# GPIO_LED_SW.net
KiCad netlist of a schematic drawn in Altium Designer
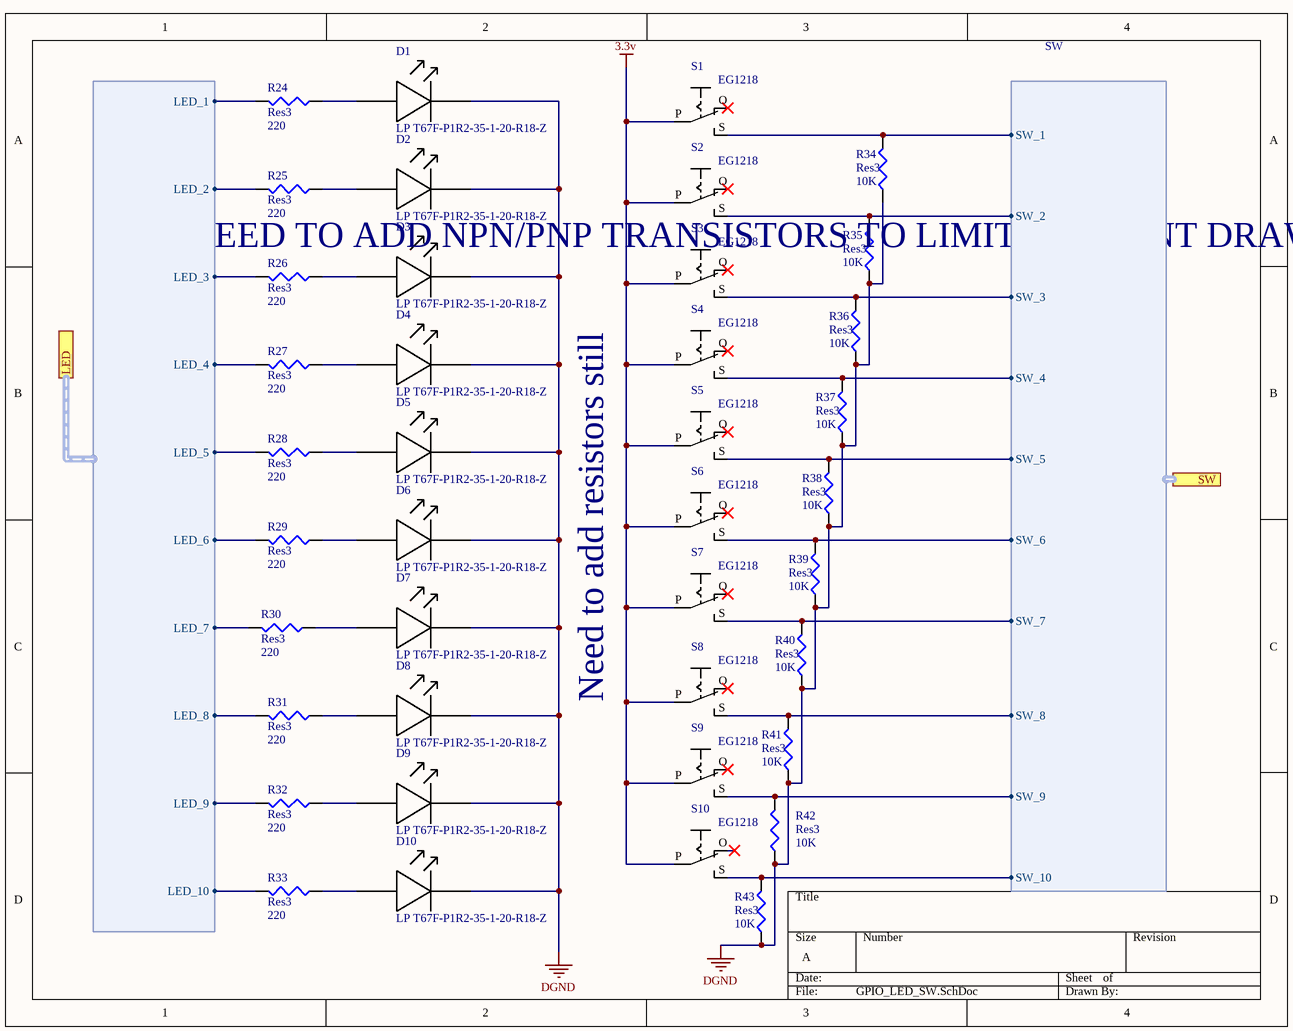
[diagram p0: GPIO_LED_SW.SchDoc]

(export (version "E")
  (design (tool "Eeschema 10.0.6"))
  (components
    (comp (ref "D1")
      (value "LP T67F-P1R2-35-1-20-R18-Z")
      (footprint "LP T67F-P1R2-35-1-20-R18-Z")
      (description "SMD LED")
      (libsource (lib "Components") (part "LP T67F-P1R2-35-1-20-R18-Z"))
    )
    (comp (ref "D2")
      (value "LP T67F-P1R2-35-1-20-R18-Z")
      (footprint "LP T67F-P1R2-35-1-20-R18-Z")
      (description "SMD LED")
      (libsource (lib "Components") (part "LP T67F-P1R2-35-1-20-R18-Z"))
    )
    (comp (ref "D3")
      (value "LP T67F-P1R2-35-1-20-R18-Z")
      (footprint "LP T67F-P1R2-35-1-20-R18-Z")
      (description "SMD LED")
      (libsource (lib "Components") (part "LP T67F-P1R2-35-1-20-R18-Z"))
    )
    (comp (ref "D4")
      (value "LP T67F-P1R2-35-1-20-R18-Z")
      (footprint "LP T67F-P1R2-35-1-20-R18-Z")
      (description "SMD LED")
      (libsource (lib "Components") (part "LP T67F-P1R2-35-1-20-R18-Z"))
    )
    (comp (ref "D5")
      (value "LP T67F-P1R2-35-1-20-R18-Z")
      (footprint "LP T67F-P1R2-35-1-20-R18-Z")
      (description "SMD LED")
      (libsource (lib "Components") (part "LP T67F-P1R2-35-1-20-R18-Z"))
    )
    (comp (ref "D6")
      (value "LP T67F-P1R2-35-1-20-R18-Z")
      (footprint "LP T67F-P1R2-35-1-20-R18-Z")
      (description "SMD LED")
      (libsource (lib "Components") (part "LP T67F-P1R2-35-1-20-R18-Z"))
    )
    (comp (ref "D7")
      (value "LP T67F-P1R2-35-1-20-R18-Z")
      (footprint "LP T67F-P1R2-35-1-20-R18-Z")
      (description "SMD LED")
      (libsource (lib "Components") (part "LP T67F-P1R2-35-1-20-R18-Z"))
    )
    (comp (ref "D8")
      (value "LP T67F-P1R2-35-1-20-R18-Z")
      (footprint "LP T67F-P1R2-35-1-20-R18-Z")
      (description "SMD LED")
      (libsource (lib "Components") (part "LP T67F-P1R2-35-1-20-R18-Z"))
    )
    (comp (ref "D9")
      (value "LP T67F-P1R2-35-1-20-R18-Z")
      (footprint "LP T67F-P1R2-35-1-20-R18-Z")
      (description "SMD LED")
      (libsource (lib "Components") (part "LP T67F-P1R2-35-1-20-R18-Z"))
    )
    (comp (ref "D10")
      (value "LP T67F-P1R2-35-1-20-R18-Z")
      (footprint "LP T67F-P1R2-35-1-20-R18-Z")
      (description "SMD LED")
      (libsource (lib "Components") (part "LP T67F-P1R2-35-1-20-R18-Z"))
    )
    (comp (ref "R24")
      (value "Res3")
      (footprint "J1-0603")
      (description "Resistor")
      (fields (field (name "ALTIUM_VALUE") "220") (field (name "PUBLISHER") "Altium Limited"))
      (libsource (lib "Miscellaneous Devices") (part "Res3"))
    )
    (comp (ref "R25")
      (value "Res3")
      (footprint "J1-0603")
      (description "Resistor")
      (fields (field (name "ALTIUM_VALUE") "220") (field (name "PUBLISHER") "Altium Limited"))
      (libsource (lib "Miscellaneous Devices") (part "Res3"))
    )
    (comp (ref "R26")
      (value "Res3")
      (footprint "J1-0603")
      (description "Resistor")
      (fields (field (name "ALTIUM_VALUE") "220") (field (name "PUBLISHER") "Altium Limited"))
      (libsource (lib "Miscellaneous Devices") (part "Res3"))
    )
    (comp (ref "R27")
      (value "Res3")
      (footprint "J1-0603")
      (description "Resistor")
      (fields (field (name "ALTIUM_VALUE") "220") (field (name "PUBLISHER") "Altium Limited"))
      (libsource (lib "Miscellaneous Devices") (part "Res3"))
    )
    (comp (ref "R28")
      (value "Res3")
      (footprint "J1-0603")
      (description "Resistor")
      (fields (field (name "ALTIUM_VALUE") "220") (field (name "PUBLISHER") "Altium Limited"))
      (libsource (lib "Miscellaneous Devices") (part "Res3"))
    )
    (comp (ref "R29")
      (value "Res3")
      (footprint "J1-0603")
      (description "Resistor")
      (fields (field (name "ALTIUM_VALUE") "220") (field (name "PUBLISHER") "Altium Limited"))
      (libsource (lib "Miscellaneous Devices") (part "Res3"))
    )
    (comp (ref "R30")
      (value "Res3")
      (footprint "J1-0603")
      (description "Resistor")
      (fields (field (name "ALTIUM_VALUE") "220") (field (name "PUBLISHER") "Altium Limited"))
      (libsource (lib "Miscellaneous Devices") (part "Res3"))
    )
    (comp (ref "R31")
      (value "Res3")
      (footprint "J1-0603")
      (description "Resistor")
      (fields (field (name "ALTIUM_VALUE") "220") (field (name "PUBLISHER") "Altium Limited"))
      (libsource (lib "Miscellaneous Devices") (part "Res3"))
    )
    (comp (ref "R32")
      (value "Res3")
      (footprint "J1-0603")
      (description "Resistor")
      (fields (field (name "ALTIUM_VALUE") "220") (field (name "PUBLISHER") "Altium Limited"))
      (libsource (lib "Miscellaneous Devices") (part "Res3"))
    )
    (comp (ref "R33")
      (value "Res3")
      (footprint "J1-0603")
      (description "Resistor")
      (fields (field (name "ALTIUM_VALUE") "220") (field (name "PUBLISHER") "Altium Limited"))
      (libsource (lib "Miscellaneous Devices") (part "Res3"))
    )
    (comp (ref "R34")
      (value "Res3")
      (footprint "J1-0603")
      (description "Resistor")
      (fields (field (name "ALTIUM_VALUE") "10K") (field (name "PUBLISHER") "Altium Limited"))
      (libsource (lib "Miscellaneous Devices") (part "Res3"))
    )
    (comp (ref "R35")
      (value "Res3")
      (footprint "J1-0603")
      (description "Resistor")
      (fields (field (name "ALTIUM_VALUE") "10K") (field (name "PUBLISHER") "Altium Limited"))
      (libsource (lib "Miscellaneous Devices") (part "Res3"))
    )
    (comp (ref "R36")
      (value "Res3")
      (footprint "J1-0603")
      (description "Resistor")
      (fields (field (name "ALTIUM_VALUE") "10K") (field (name "PUBLISHER") "Altium Limited"))
      (libsource (lib "Miscellaneous Devices") (part "Res3"))
    )
    (comp (ref "R37")
      (value "Res3")
      (footprint "J1-0603")
      (description "Resistor")
      (fields (field (name "ALTIUM_VALUE") "10K") (field (name "PUBLISHER") "Altium Limited"))
      (libsource (lib "Miscellaneous Devices") (part "Res3"))
    )
    (comp (ref "R38")
      (value "Res3")
      (footprint "J1-0603")
      (description "Resistor")
      (fields (field (name "ALTIUM_VALUE") "10K") (field (name "PUBLISHER") "Altium Limited"))
      (libsource (lib "Miscellaneous Devices") (part "Res3"))
    )
    (comp (ref "R39")
      (value "Res3")
      (footprint "J1-0603")
      (description "Resistor")
      (fields (field (name "ALTIUM_VALUE") "10K") (field (name "PUBLISHER") "Altium Limited"))
      (libsource (lib "Miscellaneous Devices") (part "Res3"))
    )
    (comp (ref "R40")
      (value "Res3")
      (footprint "J1-0603")
      (description "Resistor")
      (fields (field (name "ALTIUM_VALUE") "10K") (field (name "PUBLISHER") "Altium Limited"))
      (libsource (lib "Miscellaneous Devices") (part "Res3"))
    )
    (comp (ref "R41")
      (value "Res3")
      (footprint "J1-0603")
      (description "Resistor")
      (fields (field (name "ALTIUM_VALUE") "10K") (field (name "PUBLISHER") "Altium Limited"))
      (libsource (lib "Miscellaneous Devices") (part "Res3"))
    )
    (comp (ref "R42")
      (value "Res3")
      (footprint "J1-0603")
      (description "Resistor")
      (fields (field (name "ALTIUM_VALUE") "10K") (field (name "PUBLISHER") "Altium Limited"))
      (libsource (lib "Miscellaneous Devices") (part "Res3"))
    )
    (comp (ref "R43")
      (value "Res3")
      (footprint "J1-0603")
      (description "Resistor")
      (fields (field (name "ALTIUM_VALUE") "10K") (field (name "PUBLISHER") "Altium Limited"))
      (libsource (lib "Miscellaneous Devices") (part "Res3"))
    )
    (comp (ref "S1")
      (value "EG1218")
      (footprint "*EG1218_EG1218(Primary)")
      (description "Slide Switch SPDT Through Hole")
      (fields (field (name "MF") "E-Switch") (field (name "DIGI-KEY_PART_NUMBER") "EG1903-ND"))
      (libsource (lib "Components") (part "EG1218"))
    )
    (comp (ref "S2")
      (value "EG1218")
      (footprint "*EG1218_EG1218(Primary)")
      (description "Slide Switch SPDT Through Hole")
      (fields (field (name "MF") "E-Switch") (field (name "DIGI-KEY_PART_NUMBER") "EG1903-ND"))
      (libsource (lib "Components") (part "EG1218"))
    )
    (comp (ref "S3")
      (value "EG1218")
      (footprint "*EG1218_EG1218(Primary)")
      (description "Slide Switch SPDT Through Hole")
      (fields (field (name "MF") "E-Switch") (field (name "DIGI-KEY_PART_NUMBER") "EG1903-ND"))
      (libsource (lib "Components") (part "EG1218"))
    )
    (comp (ref "S4")
      (value "EG1218")
      (footprint "*EG1218_EG1218(Primary)")
      (description "Slide Switch SPDT Through Hole")
      (fields (field (name "MF") "E-Switch") (field (name "DIGI-KEY_PART_NUMBER") "EG1903-ND"))
      (libsource (lib "Components") (part "EG1218"))
    )
    (comp (ref "S5")
      (value "EG1218")
      (footprint "*EG1218_EG1218(Primary)")
      (description "Slide Switch SPDT Through Hole")
      (fields (field (name "MF") "E-Switch") (field (name "DIGI-KEY_PART_NUMBER") "EG1903-ND"))
      (libsource (lib "Components") (part "EG1218"))
    )
    (comp (ref "S6")
      (value "EG1218")
      (footprint "*EG1218_EG1218(Primary)")
      (description "Slide Switch SPDT Through Hole")
      (fields (field (name "MF") "E-Switch") (field (name "DIGI-KEY_PART_NUMBER") "EG1903-ND"))
      (libsource (lib "Components") (part "EG1218"))
    )
    (comp (ref "S7")
      (value "EG1218")
      (footprint "*EG1218_EG1218(Primary)")
      (description "Slide Switch SPDT Through Hole")
      (fields (field (name "MF") "E-Switch") (field (name "DIGI-KEY_PART_NUMBER") "EG1903-ND"))
      (libsource (lib "Components") (part "EG1218"))
    )
    (comp (ref "S8")
      (value "EG1218")
      (footprint "*EG1218_EG1218(Primary)")
      (description "Slide Switch SPDT Through Hole")
      (fields (field (name "MF") "E-Switch") (field (name "DIGI-KEY_PART_NUMBER") "EG1903-ND"))
      (libsource (lib "Components") (part "EG1218"))
    )
    (comp (ref "S9")
      (value "EG1218")
      (footprint "*EG1218_EG1218(Primary)")
      (description "Slide Switch SPDT Through Hole")
      (fields (field (name "MF") "E-Switch") (field (name "DIGI-KEY_PART_NUMBER") "EG1903-ND"))
      (libsource (lib "Components") (part "EG1218"))
    )
    (comp (ref "S10")
      (value "EG1218")
      (footprint "*EG1218_EG1218(Primary)")
      (description "Slide Switch SPDT Through Hole")
      (fields (field (name "MF") "E-Switch") (field (name "DIGI-KEY_PART_NUMBER") "EG1903-ND"))
      (libsource (lib "Components") (part "EG1218"))
    )
  )
  (nets
    (net (code "3") (name "/LED_1") (class "Default")
      (node (ref "R24") (pin "2") (pinfunction "2_2") (pintype "passive"))
    )
    (net (code "4") (name "/LED_2") (class "Default")
      (node (ref "R25") (pin "2") (pinfunction "2_2") (pintype "passive"))
    )
    (net (code "5") (name "/LED_3") (class "Default")
      (node (ref "R26") (pin "2") (pinfunction "2_2") (pintype "passive"))
    )
    (net (code "6") (name "/LED_4") (class "Default")
      (node (ref "R27") (pin "2") (pinfunction "2_2") (pintype "passive"))
    )
    (net (code "7") (name "/LED_5") (class "Default")
      (node (ref "R28") (pin "2") (pinfunction "2_2") (pintype "passive"))
    )
    (net (code "8") (name "/LED_6") (class "Default")
      (node (ref "R29") (pin "2") (pinfunction "2_2") (pintype "passive"))
    )
    (net (code "9") (name "/LED_7") (class "Default")
      (node (ref "R30") (pin "2") (pinfunction "2_2") (pintype "passive"))
    )
    (net (code "10") (name "/LED_8") (class "Default")
      (node (ref "R31") (pin "2") (pinfunction "2_2") (pintype "passive"))
    )
    (net (code "11") (name "/LED_9") (class "Default")
      (node (ref "R32") (pin "2") (pinfunction "2_2") (pintype "passive"))
    )
    (net (code "12") (name "/LED_10") (class "Default")
      (node (ref "R33") (pin "2") (pinfunction "2_2") (pintype "passive"))
    )
    (net (code "13") (name "/SW_1") (class "Default")
      (node (ref "R34") (pin "2") (pinfunction "2_2") (pintype "passive"))
      (node (ref "S1") (pin "S") (pinfunction "S_S") (pintype "passive"))
    )
    (net (code "14") (name "/SW_2") (class "Default")
      (node (ref "R35") (pin "2") (pinfunction "2_2") (pintype "passive"))
      (node (ref "S2") (pin "S") (pinfunction "S_S") (pintype "passive"))
    )
    (net (code "15") (name "/SW_3") (class "Default")
      (node (ref "R36") (pin "2") (pinfunction "2_2") (pintype "passive"))
      (node (ref "S3") (pin "S") (pinfunction "S_S") (pintype "passive"))
    )
    (net (code "16") (name "/SW_4") (class "Default")
      (node (ref "R37") (pin "2") (pinfunction "2_2") (pintype "passive"))
      (node (ref "S4") (pin "S") (pinfunction "S_S") (pintype "passive"))
    )
    (net (code "17") (name "/SW_5") (class "Default")
      (node (ref "R38") (pin "2") (pinfunction "2_2") (pintype "passive"))
      (node (ref "S5") (pin "S") (pinfunction "S_S") (pintype "passive"))
    )
    (net (code "18") (name "/SW_6") (class "Default")
      (node (ref "R39") (pin "2") (pinfunction "2_2") (pintype "passive"))
      (node (ref "S6") (pin "S") (pinfunction "S_S") (pintype "passive"))
    )
    (net (code "19") (name "/SW_7") (class "Default")
      (node (ref "R40") (pin "2") (pinfunction "2_2") (pintype "passive"))
      (node (ref "S7") (pin "S") (pinfunction "S_S") (pintype "passive"))
    )
    (net (code "20") (name "/SW_8") (class "Default")
      (node (ref "R41") (pin "2") (pinfunction "2_2") (pintype "passive"))
      (node (ref "S8") (pin "S") (pinfunction "S_S") (pintype "passive"))
    )
    (net (code "21") (name "/SW_9") (class "Default")
      (node (ref "R42") (pin "2") (pinfunction "2_2") (pintype "passive"))
      (node (ref "S9") (pin "S") (pinfunction "S_S") (pintype "passive"))
    )
    (net (code "22") (name "/SW_10") (class "Default")
      (node (ref "R43") (pin "2") (pinfunction "2_2") (pintype "passive"))
      (node (ref "S10") (pin "S") (pinfunction "S_S") (pintype "passive"))
    )
    (net (code "25") (name "3.3v") (class "Default")
      (node (ref "S1") (pin "P") (pinfunction "P_P") (pintype "passive"))
      (node (ref "S10") (pin "P") (pinfunction "P_P") (pintype "passive"))
      (node (ref "S2") (pin "P") (pinfunction "P_P") (pintype "passive"))
      (node (ref "S3") (pin "P") (pinfunction "P_P") (pintype "passive"))
      (node (ref "S4") (pin "P") (pinfunction "P_P") (pintype "passive"))
      (node (ref "S5") (pin "P") (pinfunction "P_P") (pintype "passive"))
      (node (ref "S6") (pin "P") (pinfunction "P_P") (pintype "passive"))
      (node (ref "S7") (pin "P") (pinfunction "P_P") (pintype "passive"))
      (node (ref "S8") (pin "P") (pinfunction "P_P") (pintype "passive"))
      (node (ref "S9") (pin "P") (pinfunction "P_P") (pintype "passive"))
    )
    (net (code "26") (name "DGND") (class "Default")
      (node (ref "D1") (pin "C") (pinfunction "C_C") (pintype "passive"))
      (node (ref "D10") (pin "C") (pinfunction "C_C") (pintype "passive"))
      (node (ref "D2") (pin "C") (pinfunction "C_C") (pintype "passive"))
      (node (ref "D3") (pin "C") (pinfunction "C_C") (pintype "passive"))
      (node (ref "D4") (pin "C") (pinfunction "C_C") (pintype "passive"))
      (node (ref "D5") (pin "C") (pinfunction "C_C") (pintype "passive"))
      (node (ref "D6") (pin "C") (pinfunction "C_C") (pintype "passive"))
      (node (ref "D7") (pin "C") (pinfunction "C_C") (pintype "passive"))
      (node (ref "D8") (pin "C") (pinfunction "C_C") (pintype "passive"))
      (node (ref "D9") (pin "C") (pinfunction "C_C") (pintype "passive"))
      (node (ref "R34") (pin "1") (pinfunction "1_1") (pintype "passive"))
      (node (ref "R35") (pin "1") (pinfunction "1_1") (pintype "passive"))
      (node (ref "R36") (pin "1") (pinfunction "1_1") (pintype "passive"))
      (node (ref "R37") (pin "1") (pinfunction "1_1") (pintype "passive"))
      (node (ref "R38") (pin "1") (pinfunction "1_1") (pintype "passive"))
      (node (ref "R39") (pin "1") (pinfunction "1_1") (pintype "passive"))
      (node (ref "R40") (pin "1") (pinfunction "1_1") (pintype "passive"))
      (node (ref "R41") (pin "1") (pinfunction "1_1") (pintype "passive"))
      (node (ref "R42") (pin "1") (pinfunction "1_1") (pintype "passive"))
      (node (ref "R43") (pin "1") (pinfunction "1_1") (pintype "passive"))
    )
    (net (code "27") (name "Net-(D1-PadA)") (class "Default")
      (node (ref "D1") (pin "A") (pinfunction "A_A") (pintype "passive"))
      (node (ref "R24") (pin "1") (pinfunction "1_1") (pintype "passive"))
    )
    (net (code "28") (name "Net-(D2-PadA)") (class "Default")
      (node (ref "D2") (pin "A") (pinfunction "A_A") (pintype "passive"))
      (node (ref "R25") (pin "1") (pinfunction "1_1") (pintype "passive"))
    )
    (net (code "29") (name "Net-(D3-PadA)") (class "Default")
      (node (ref "D3") (pin "A") (pinfunction "A_A") (pintype "passive"))
      (node (ref "R26") (pin "1") (pinfunction "1_1") (pintype "passive"))
    )
    (net (code "30") (name "Net-(D4-PadA)") (class "Default")
      (node (ref "D4") (pin "A") (pinfunction "A_A") (pintype "passive"))
      (node (ref "R27") (pin "1") (pinfunction "1_1") (pintype "passive"))
    )
    (net (code "31") (name "Net-(D5-PadA)") (class "Default")
      (node (ref "D5") (pin "A") (pinfunction "A_A") (pintype "passive"))
      (node (ref "R28") (pin "1") (pinfunction "1_1") (pintype "passive"))
    )
    (net (code "32") (name "Net-(D6-PadA)") (class "Default")
      (node (ref "D6") (pin "A") (pinfunction "A_A") (pintype "passive"))
      (node (ref "R29") (pin "1") (pinfunction "1_1") (pintype "passive"))
    )
    (net (code "33") (name "Net-(D7-PadA)") (class "Default")
      (node (ref "D7") (pin "A") (pinfunction "A_A") (pintype "passive"))
      (node (ref "R30") (pin "1") (pinfunction "1_1") (pintype "passive"))
    )
    (net (code "34") (name "Net-(D8-PadA)") (class "Default")
      (node (ref "D8") (pin "A") (pinfunction "A_A") (pintype "passive"))
      (node (ref "R31") (pin "1") (pinfunction "1_1") (pintype "passive"))
    )
    (net (code "35") (name "Net-(D9-PadA)") (class "Default")
      (node (ref "D9") (pin "A") (pinfunction "A_A") (pintype "passive"))
      (node (ref "R32") (pin "1") (pinfunction "1_1") (pintype "passive"))
    )
    (net (code "36") (name "Net-(D10-PadA)") (class "Default")
      (node (ref "D10") (pin "A") (pinfunction "A_A") (pintype "passive"))
      (node (ref "R33") (pin "1") (pinfunction "1_1") (pintype "passive"))
    )
    (net (code "37") (name "unconnected-(S1-PadO)") (class "Default")
      (node (ref "S1") (pin "O") (pinfunction "O_O") (pintype "passive+no_connect"))
    )
    (net (code "38") (name "unconnected-(S2-PadO)") (class "Default")
      (node (ref "S2") (pin "O") (pinfunction "O_O") (pintype "passive+no_connect"))
    )
    (net (code "39") (name "unconnected-(S3-PadO)") (class "Default")
      (node (ref "S3") (pin "O") (pinfunction "O_O") (pintype "passive+no_connect"))
    )
    (net (code "40") (name "unconnected-(S4-PadO)") (class "Default")
      (node (ref "S4") (pin "O") (pinfunction "O_O") (pintype "passive+no_connect"))
    )
    (net (code "41") (name "unconnected-(S5-PadO)") (class "Default")
      (node (ref "S5") (pin "O") (pinfunction "O_O") (pintype "passive+no_connect"))
    )
    (net (code "42") (name "unconnected-(S6-PadO)") (class "Default")
      (node (ref "S6") (pin "O") (pinfunction "O_O") (pintype "passive+no_connect"))
    )
    (net (code "43") (name "unconnected-(S7-PadO)") (class "Default")
      (node (ref "S7") (pin "O") (pinfunction "O_O") (pintype "passive+no_connect"))
    )
    (net (code "44") (name "unconnected-(S8-PadO)") (class "Default")
      (node (ref "S8") (pin "O") (pinfunction "O_O") (pintype "passive+no_connect"))
    )
    (net (code "45") (name "unconnected-(S9-PadO)") (class "Default")
      (node (ref "S9") (pin "O") (pinfunction "O_O") (pintype "passive+no_connect"))
    )
    (net (code "46") (name "unconnected-(S10-PadO)") (class "Default")
      (node (ref "S10") (pin "O") (pinfunction "O_O") (pintype "passive+no_connect"))
    )
  )
)
